# POWER.net
KiCad netlist of a schematic drawn in Altium Designer
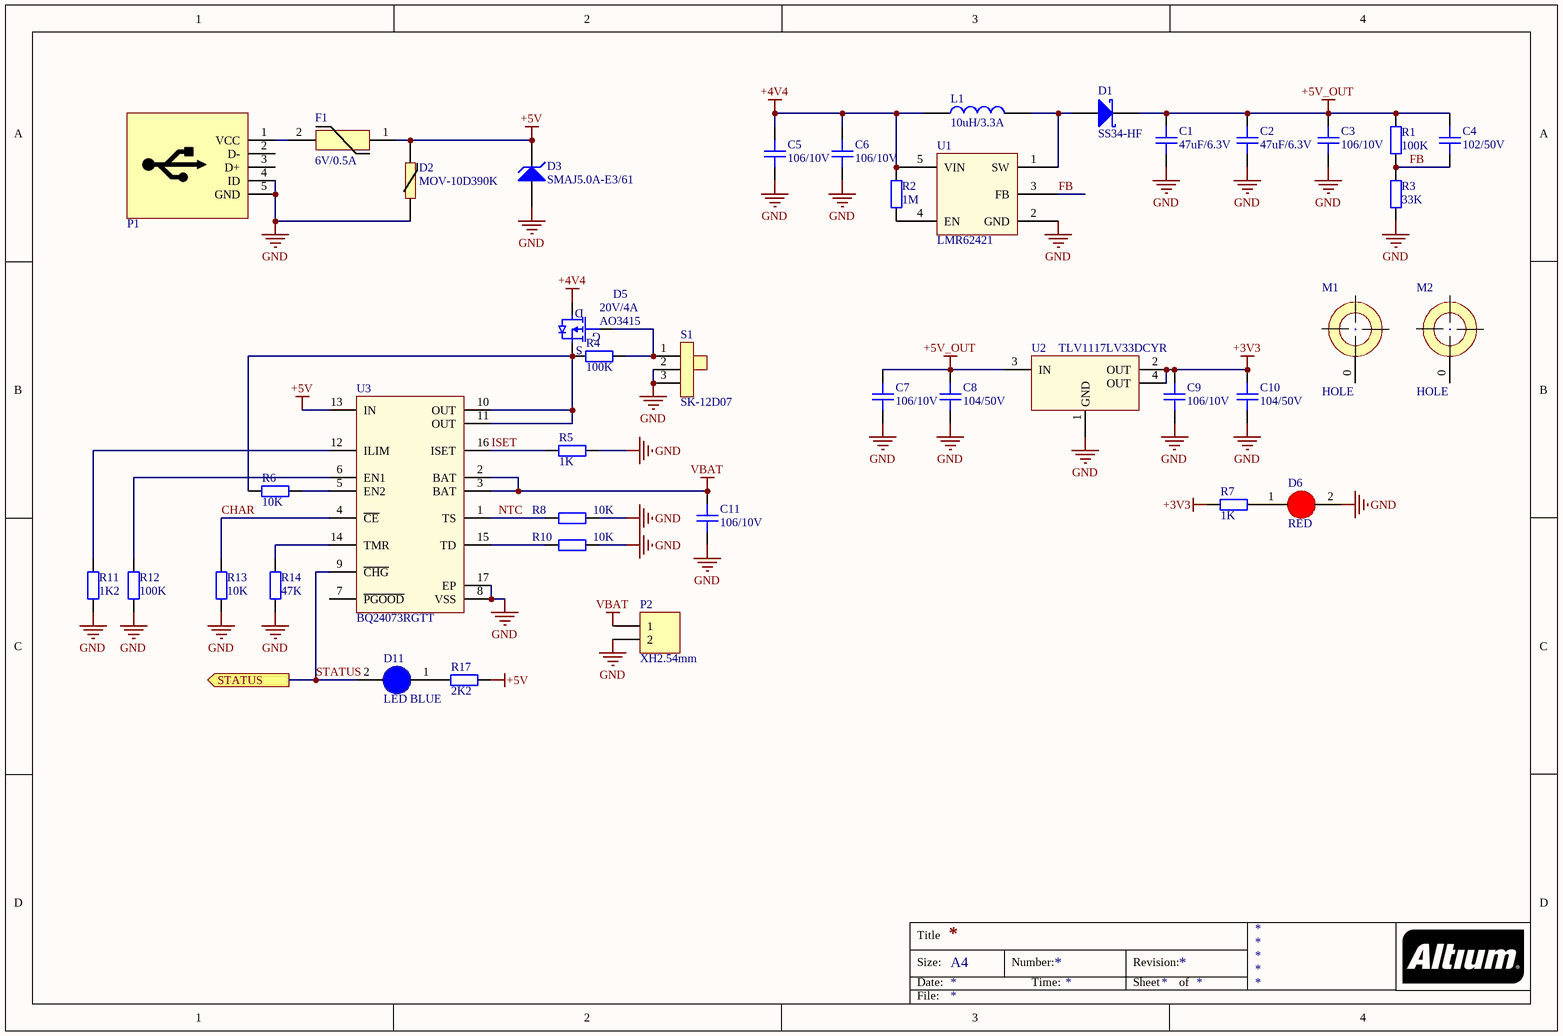
[diagram p0: POWER.SchDoc]

(export (version "E")
  (design (tool "Eeschema 10.0.6"))
  (components
    (comp (ref "C1")
      (value "47uF/6.3V")
      (footprint "CAPC-0603 (1608) - HD")
      (description "CAP CER 47UF 6.3V X5R 0603")
      (fields (field (name "MPN") "GRM188R60J476ME15D") (field (name "MFR") "Murata Electronics"))
      (libsource (lib "01.Passives 2") (part "GRM188R60J476ME15D"))
    )
    (comp (ref "C2")
      (value "47uF/6.3V")
      (footprint "CAPC-0603 (1608) - HD")
      (description "CAP CER 47UF 6.3V X5R 0603")
      (fields (field (name "MPN") "GRM188R60J476ME15D") (field (name "MFR") "Murata Electronics"))
      (libsource (lib "01.Passives 2") (part "GRM188R60J476ME15D"))
    )
    (comp (ref "C3")
      (value "106/10V")
      (footprint "CAPC-0603 (1608) - HD")
      (description "CAP CER 10uF 10% 10V X5R 0603")
      (fields (field (name "MPN") "CL10A106KP8NNNC") (field (name "MFR") "Samsung Electro-Mechanics"))
      (libsource (lib "01.Passives 2") (part "CL10A106KP8NNNC"))
    )
    (comp (ref "C4")
      (value "102/50V")
      (footprint "CAPC-0603 (1608) - HD")
      (description "CAP CER 1000pF 10% 50V X7R 0603")
      (fields (field (name "MPN") "CL10B102KB8NNNC"))
      (libsource (lib "01.Passives 2") (part "CL10B102KB8NNNC"))
    )
    (comp (ref "C5")
      (value "106/10V")
      (footprint "CAPC-0603 (1608) - HD")
      (description "CAP CER 10uF 10% 10V X5R 0603")
      (fields (field (name "MPN") "CL10A106KP8NNNC") (field (name "MFR") "Samsung Electro-Mechanics"))
      (libsource (lib "01.Passives 2") (part "CL10A106KP8NNNC"))
    )
    (comp (ref "C6")
      (value "106/10V")
      (footprint "CAPC-0603 (1608) - HD")
      (description "CAP CER 10uF 10% 10V X5R 0603")
      (fields (field (name "MPN") "CL10A106KP8NNNC") (field (name "MFR") "Samsung Electro-Mechanics"))
      (libsource (lib "01.Passives 2") (part "CL10A106KP8NNNC"))
    )
    (comp (ref "C7")
      (value "106/10V")
      (footprint "CAPC-0603 (1608) - HD")
      (description "CAP CER 10uF 10% 10V X5R 0603")
      (fields (field (name "MPN") "CL10A106KP8NNNC"))
      (libsource (lib "01.Passives") (part "CL10A106KP8NNNC"))
    )
    (comp (ref "C8")
      (value "104/50V")
      (footprint "CAPC-0603 (1608) - HD")
      (description "CAP CER 0.1uF 50V 10% X7R 0603")
      (fields (field (name "MPN") "C0603C104K5RACTU"))
      (libsource (lib "01.Passives") (part "C0603C104K5RACTU"))
    )
    (comp (ref "C9")
      (value "106/10V")
      (footprint "CAPC-0603 (1608) - HD")
      (description "CAP CER 10uF 10% 10V X5R 0603")
      (fields (field (name "MPN") "CL10A106KP8NNNC"))
      (libsource (lib "01.Passives") (part "CL10A106KP8NNNC"))
    )
    (comp (ref "C10")
      (value "104/50V")
      (footprint "CAPC-0603 (1608) - HD")
      (description "CAP CER 0.1uF 50V 10% X7R 0603")
      (fields (field (name "MPN") "C0603C104K5RACTU"))
      (libsource (lib "01.Passives") (part "C0603C104K5RACTU"))
    )
    (comp (ref "C11")
      (value "106/10V")
      (footprint "CAPC-0603 (1608) - HD")
      (description "CAP CER 10uF 10% 10V X5R 0603")
      (fields (field (name "MPN") "CL10A106KP8NNNC") (field (name "MFR") "Samsung Electro-Mechanics"))
      (libsource (lib "01.Passives 2") (part "CL10A106KP8NNNC"))
    )
    (comp (ref "D1")
      (value "SS34-HF")
      (footprint "DIODE_DO214AC_SMA")
      (description "DIODE SCHOTTKY 40V 3A SMA")
      (fields (field (name "MFR") "onsemi"))
      (libsource (lib "03.Semiconductor(1)") (part "SS34-HF"))
    )
    (comp (ref "D2")
      (value "MOV-10D390K")
      (footprint "MOV-07D101KTR")
      (description "VARISTOR 39V 500A DISC 10MM")
      (fields (field (name "MFR") "Bourns Inc.") (field (name "MPN") "MOV-10D390K"))
      (libsource (lib "01.Passives 2") (part "MOV-10D390K"))
    )
    (comp (ref "D3")
      (value "SMAJ5.0A-E3/61")
      (footprint "DIODE_DO214AC_SMA")
      (description "DIODE TVS 5VWM 9.2VC SMA")
      (libsource (lib "03.Semiconductor(1)") (part "SMAJ5.0A-E3/61"))
    )
    (comp (ref "D5")
      (value "20V/4A")
      (footprint "SOT23_3")
      (description "MOSFET P-CH 20V 4A SOT23")
      (fields (field (name "MFR") "Alpha & Omega Semiconductor Inc.") (field (name "MPN") "AO3415"))
      (libsource (lib "03.Semiconductor(1)") (part "AO3415"))
    )
    (comp (ref "D6")
      (value "RED")
      (footprint "LED 0603")
      (description "LED 0603 RED")
      (libsource (lib "03.Semiconductor(1)") (part "LED 0603 RED"))
    )
    (comp (ref "D11")
      (value "LED BLUE")
      (footprint "LED_3MM-RED - duplicate")
      (description "LED BLUE 3MM ROUND T/H")
      (fields (field (name "MPN") "LED BLUE 3MM") (field (name "MFR") "China"))
      (libsource (lib "03.Semiconductor(1)") (part "LED BLUE 3MM"))
    )
    (comp (ref "F1")
      (value "6V/0.5A")
      (footprint "FUSE 0ZCK_BEL")
      (description "PTC RESET FUSE 6V 500MA 0805")
      (fields (field (name "MPN") "0ZCK0050FF2E") (field (name "MANUFACTURER") "Bel Fuse Inc."))
      (libsource (lib "02.Power,Protection") (part "0ZCK0050FF2E"))
    )
    (comp (ref "L1")
      (value "10uH/3.3A")
      (footprint "IND-74404084150")
      (description "FIXED IND 10UH 3.3A 38 MOHM SMD")
      (fields
        (field (name "MPN") "SWPA8040S100MT")
        (field (name "MFR") "Shenzhen Sunlord Electronics Co., Ltd.")
      )
      (libsource (lib "01.Passives 2") (part "SWPA8040S100MT"))
    )
    (comp (ref "M1")
      (value "HOLE")
      (footprint "HOLE_3MM_6MM")
      (description "HOLE 2_4/2_5/3_5/3_6")
      (fields (field (name "MPN") "None"))
      (libsource (lib "04.Header-Connecter") (part "HOLE_2_4/2_5/3_5/3_6"))
    )
    (comp (ref "M2")
      (value "HOLE")
      (footprint "HOLE_3MM_6MM")
      (description "HOLE 2_4/2_5/3_5/3_6")
      (fields (field (name "MPN") "None"))
      (libsource (lib "04.Header-Connecter") (part "HOLE_2_4/2_5/3_5/3_6"))
    )
    (comp (ref "P1")
      (value "Micro USB")
      (footprint "MK5P MICROUSB")
      (description "Micro USB Right Angle MK5P DIP")
      (fields (field (name "MPN") "MK5P_DIP") (field (name "MFR") "China"))
      (libsource (lib "04.Header-Connecter") (part "MK5P_DIP"))
    )
    (comp (ref "P2")
      (value "XH2.54mm")
      (footprint "XH2.54-2P")
      (description "XH2.54mmm - 2P 180 degree")
      (fields (field (name "MPN") "XH2.54-2P") (field (name "MFR") "China"))
      (libsource (lib "04.Header-Connecter") (part "XH2.54-2P"))
    )
    (comp (ref "R1")
      (value "100K")
      (footprint "RESC-0603 (1608) - HD")
      (description "RES SMD 100K OHM 1% 1/10W 0603")
      (fields (field (name "MPN") "RC0603FR-07100KL") (field (name "MFR") "Yageo"))
      (libsource (lib "01.Passives 2") (part "RC0603FR-07100KL"))
    )
    (comp (ref "R2")
      (value "1M")
      (footprint "RESC-0603 (1608) - HD")
      (description "RES SMD 1M OHM 1% 1/10W 0603")
      (fields (field (name "MPN") "CRCW06031M00FKEA") (field (name "MFR") "Vishay Dale"))
      (libsource (lib "01.Passives 2") (part "CRCW06031M00FKEA"))
    )
    (comp (ref "R3")
      (value "33K")
      (footprint "RESC-0603 (1608) - HD")
      (description "RES SMD 33K OHM 1% 1/10W 0603")
      (fields (field (name "MPN") "RC0603FR-0733KL"))
      (libsource (lib "01.Passives 2") (part "RC0603FR-0733KL"))
    )
    (comp (ref "R4")
      (value "100K")
      (footprint "RESC-0603 (1608) - HD")
      (description "RES SMD 100K OHM 1% 1/10W 0603")
      (fields (field (name "MPN") "RC0603FR-07100KL") (field (name "MFR") "Yageo"))
      (libsource (lib "") (part "RC0603FR-07100KL_1"))
    )
    (comp (ref "R5")
      (value "1K")
      (footprint "RESC-0603 (1608) - HD")
      (description "RES SMD 1 KOHM 1% 1/10W 0603")
      (fields (field (name "MPN") "RC0603FR-071KL"))
      (libsource (lib "01.Passives 2") (part "RC0603FR-071KL"))
    )
    (comp (ref "R6")
      (value "10K")
      (footprint "RESC-0603 (1608) - HD")
      (description "RES SMD 10K OHM 1% 1/10W 0603")
      (fields (field (name "MPN") "RC0603FR-0710KL"))
      (libsource (lib "") (part "RC0603FR-0710KL_1"))
    )
    (comp (ref "R7")
      (value "1K")
      (footprint "RESC-0603 (1608) - HD")
      (description "RES SMD 1 KOHM 1% 1/10W 0603")
      (fields (field (name "MPN") "RC0603FR-071KL"))
      (libsource (lib "01.Passives 2") (part "RC0603FR-071KL"))
    )
    (comp (ref "R8")
      (value "10K")
      (footprint "RESC-0603 (1608) - HD")
      (description "RES SMD 10K OHM 1% 1/10W 0603")
      (fields (field (name "MPN") "RC0603FR-0710KL"))
      (libsource (lib "") (part "RC0603FR-0710KL_1"))
    )
    (comp (ref "R10")
      (value "10K")
      (footprint "RESC-0603 (1608) - HD")
      (description "RES SMD 10K OHM 1% 1/10W 0603")
      (fields (field (name "MPN") "RC0603FR-0710KL"))
      (libsource (lib "") (part "RC0603FR-0710KL_1"))
    )
    (comp (ref "R11")
      (value "1K2")
      (footprint "RESC-0603 (1608) - HD")
      (description "RES SMD 1.2K OHM 1% 1/10W 0603")
      (fields (field (name "MPN") "RC0603FR-071K2L"))
      (libsource (lib "01.Passives") (part "RC0603FR-071K2L"))
    )
    (comp (ref "R12")
      (value "100K")
      (footprint "RESC-0603 (1608) - HD")
      (description "RES SMD 100K OHM 1% 1/10W 0603")
      (fields (field (name "MPN") "RC0603FR-07100KL"))
      (libsource (lib "01.Passives") (part "RC0603FR-07100KL"))
    )
    (comp (ref "R13")
      (value "10K")
      (footprint "RESC-0603 (1608) - HD")
      (description "RES SMD 10K OHM 1% 1/10W 0603")
      (fields (field (name "MPN") "RC0603FR-0710KL"))
      (libsource (lib "01.Passives") (part "RC0603FR-0710KL"))
    )
    (comp (ref "R14")
      (value "47K")
      (footprint "RESC-0603 (1608) - HD")
      (description "RES SMD 47K OHM 1% 1/10W 0603")
      (fields (field (name "MPN") "RC0603FR0747KL"))
      (libsource (lib "01.Passives") (part "RC0603FR0747KL"))
    )
    (comp (ref "R17")
      (value "2K2")
      (footprint "RESC-0603 (1608) - HD")
      (description "RES SMD 2.2K OHM 1% 1/10W 0603")
      (fields (field (name "MPN") "CRCW06032K20FKEA"))
      (libsource (lib "01.Passives") (part "CRCW06032K20FKEA"))
    )
    (comp (ref "S1")
      (value "SK-12D07")
      (footprint "SK-12D07")
      (description "SK-12D07 Switch 5P")
      (fields (field (name "MFR") "ChinaDaier"))
      (libsource (lib "08.Miscellaneous") (part "SK-12D07"))
    )
    (comp (ref "U1")
      (value "LMR62421")
      (footprint "SC-74A")
      (description "IC REG BST SEPIC ADJ 2.1A SOT23")
      (fields (field (name "MPN") "LMR62421XMFX/NOPB") (field (name "MFR") "TI"))
      (libsource (lib "05.IC(1)") (part "LMR62421XMFX/NOPB"))
    )
    (comp (ref "U2")
      (value "TLV1117LV33DCYR")
      (footprint "SOT-223-4")
      (description "IC REG LINEAR 3.3V 1A SOT223-4")
      (libsource (lib "05.IC") (part "TLV1117LV33DCYR"))
    )
    (comp (ref "U3")
      (value "BQ24073RGTT")
      (footprint "RGT16-1700X1700TP")
      (description "IC LI-ION CHARGE/PWR MGMT 16-QFN")
      (fields (field (name "MFR") "Texas Instruments"))
      (libsource (lib "05.IC") (part "BQ24073RGTT"))
    )
  )
  (nets
    (net (code "1") (name "+3V3") (class "Default")
      (node (ref "C10") (pin "2") (pinfunction "2_2") (pintype "passive"))
      (node (ref "C9") (pin "2") (pinfunction "2_2") (pintype "passive"))
      (node (ref "R7") (pin "1") (pinfunction "1_1") (pintype "passive"))
      (node (ref "U2") (pin "2") (pinfunction "OUT_2") (pintype "passive"))
      (node (ref "U2") (pin "4") (pinfunction "OUT_4") (pintype "passive"))
    )
    (net (code "2") (name "+4V4") (class "Default")
      (node (ref "C5") (pin "2") (pinfunction "2_2") (pintype "passive"))
      (node (ref "C6") (pin "2") (pinfunction "2_2") (pintype "passive"))
      (node (ref "D5") (pin "3") (pinfunction "D_3") (pintype "passive"))
      (node (ref "L1") (pin "1") (pinfunction "1_1") (pintype "passive"))
      (node (ref "R2") (pin "2") (pinfunction "2_2") (pintype "passive"))
      (node (ref "U1") (pin "5") (pinfunction "VIN_5") (pintype "passive"))
    )
    (net (code "3") (name "+5V") (class "Default")
      (node (ref "D2") (pin "2") (pinfunction "K_2") (pintype "passive"))
      (node (ref "D3") (pin "2") (pinfunction "K_2") (pintype "passive"))
      (node (ref "F1") (pin "1") (pinfunction "1_1") (pintype "passive"))
      (node (ref "R17") (pin "2") (pinfunction "2_2") (pintype "passive"))
      (node (ref "U3") (pin "13") (pinfunction "IN_13") (pintype "power_in"))
    )
    (net (code "4") (name "+5V_OUT") (class "Default")
      (node (ref "C1") (pin "2") (pinfunction "2_2") (pintype "passive"))
      (node (ref "C2") (pin "2") (pinfunction "2_2") (pintype "passive"))
      (node (ref "C3") (pin "2") (pinfunction "2_2") (pintype "passive"))
      (node (ref "C4") (pin "2") (pinfunction "2_2") (pintype "passive"))
      (node (ref "C7") (pin "2") (pinfunction "2_2") (pintype "passive"))
      (node (ref "C8") (pin "2") (pinfunction "2_2") (pintype "passive"))
      (node (ref "D1") (pin "2") (pinfunction "K_2") (pintype "passive"))
      (node (ref "R1") (pin "2") (pinfunction "2_2") (pintype "passive"))
      (node (ref "U2") (pin "3") (pinfunction "IN_3") (pintype "passive"))
    )
    (net (code "5") (name "/CHAR") (class "Default")
      (node (ref "R13") (pin "2") (pinfunction "2_2") (pintype "passive"))
      (node (ref "U3") (pin "4") (pinfunction "~{CE}_4") (pintype "passive"))
    )
    (net (code "6") (name "/FB") (class "Default")
      (node (ref "C4") (pin "1") (pinfunction "1_1") (pintype "passive"))
      (node (ref "R1") (pin "1") (pinfunction "1_1") (pintype "passive"))
      (node (ref "R3") (pin "2") (pinfunction "2_2") (pintype "passive"))
      (node (ref "U1") (pin "3") (pinfunction "FB_3") (pintype "passive"))
    )
    (net (code "7") (name "/ISET") (class "Default")
      (node (ref "R5") (pin "1") (pinfunction "1_1") (pintype "passive"))
      (node (ref "U3") (pin "16") (pinfunction "ISET_16") (pintype "power_in"))
    )
    (net (code "8") (name "/NTC") (class "Default")
      (node (ref "R8") (pin "1") (pinfunction "1_1") (pintype "passive"))
      (node (ref "U3") (pin "1") (pinfunction "TS_1") (pintype "power_in"))
    )
    (net (code "9") (name "/STATUS") (class "Default")
      (node (ref "D11") (pin "2") (pinfunction "K_2") (pintype "passive"))
      (node (ref "U3") (pin "9") (pinfunction "~{CHG}_9") (pintype "power_in"))
    )
    (net (code "10") (name "GND") (class "Default")
      (node (ref "C1") (pin "1") (pinfunction "1_1") (pintype "passive"))
      (node (ref "C10") (pin "1") (pinfunction "1_1") (pintype "passive"))
      (node (ref "C11") (pin "1") (pinfunction "1_1") (pintype "passive"))
      (node (ref "C2") (pin "1") (pinfunction "1_1") (pintype "passive"))
      (node (ref "C3") (pin "1") (pinfunction "1_1") (pintype "passive"))
      (node (ref "C5") (pin "1") (pinfunction "1_1") (pintype "passive"))
      (node (ref "C6") (pin "1") (pinfunction "1_1") (pintype "passive"))
      (node (ref "C7") (pin "1") (pinfunction "1_1") (pintype "passive"))
      (node (ref "C8") (pin "1") (pinfunction "1_1") (pintype "passive"))
      (node (ref "C9") (pin "1") (pinfunction "1_1") (pintype "passive"))
      (node (ref "D2") (pin "1") (pinfunction "A_1") (pintype "passive"))
      (node (ref "D3") (pin "1") (pinfunction "A_1") (pintype "passive"))
      (node (ref "D6") (pin "2") (pinfunction "K_2") (pintype "passive"))
      (node (ref "P1") (pin "4") (pinfunction "ID_4") (pintype "passive"))
      (node (ref "P1") (pin "5") (pinfunction "GND_5") (pintype "passive"))
      (node (ref "P2") (pin "2") (pinfunction "2_2") (pintype "passive"))
      (node (ref "R10") (pin "2") (pinfunction "2_2") (pintype "passive"))
      (node (ref "R11") (pin "1") (pinfunction "1_1") (pintype "passive"))
      (node (ref "R12") (pin "1") (pinfunction "1_1") (pintype "passive"))
      (node (ref "R13") (pin "1") (pinfunction "1_1") (pintype "passive"))
      (node (ref "R14") (pin "1") (pinfunction "1_1") (pintype "passive"))
      (node (ref "R3") (pin "1") (pinfunction "1_1") (pintype "passive"))
      (node (ref "R5") (pin "2") (pinfunction "2_2") (pintype "passive"))
      (node (ref "R8") (pin "2") (pinfunction "2_2") (pintype "passive"))
      (node (ref "S1") (pin "2") (pinfunction "+_2") (pintype "power_in"))
      (node (ref "S1") (pin "3") (pinfunction "+_3") (pintype "power_in"))
      (node (ref "U1") (pin "2") (pinfunction "GND_2") (pintype "passive"))
      (node (ref "U2") (pin "1") (pinfunction "GND_1") (pintype "passive"))
      (node (ref "U3") (pin "17") (pinfunction "EP_17") (pintype "power_in"))
      (node (ref "U3") (pin "8") (pinfunction "VSS_8") (pintype "power_in"))
    )
    (net (code "11") (name "Net-(D1-A)") (class "Default")
      (node (ref "D1") (pin "1") (pinfunction "A_1") (pintype "passive"))
      (node (ref "L1") (pin "2") (pinfunction "2_2") (pintype "passive"))
      (node (ref "U1") (pin "1") (pinfunction "SW_1") (pintype "passive"))
    )
    (net (code "12") (name "Net-(D5-G)") (class "Default")
      (node (ref "D5") (pin "1") (pinfunction "G_1") (pintype "passive"))
      (node (ref "R4") (pin "1") (pinfunction "1_1") (pintype "passive"))
      (node (ref "S1") (pin "1") (pinfunction "+_1") (pintype "power_in"))
    )
    (net (code "13") (name "Net-(D5-S)") (class "Default")
      (node (ref "D5") (pin "2") (pinfunction "S_2") (pintype "passive"))
      (node (ref "R4") (pin "2") (pinfunction "2_2") (pintype "passive"))
      (node (ref "R6") (pin "1") (pinfunction "1_1") (pintype "passive"))
      (node (ref "U3") (pin "10") (pinfunction "OUT_10") (pintype "power_in"))
      (node (ref "U3") (pin "11") (pinfunction "OUT_11") (pintype "power_in"))
    )
    (net (code "14") (name "Net-(D6-A)") (class "Default")
      (node (ref "D6") (pin "1") (pinfunction "A_1") (pintype "passive"))
      (node (ref "R7") (pin "2") (pinfunction "2_2") (pintype "passive"))
    )
    (net (code "15") (name "Net-(D11-A)") (class "Default")
      (node (ref "D11") (pin "1") (pinfunction "A_1") (pintype "passive"))
      (node (ref "R17") (pin "1") (pinfunction "1_1") (pintype "passive"))
    )
    (net (code "16") (name "Net-(P1-VCC)") (class "Default")
      (node (ref "F1") (pin "2") (pinfunction "2_2") (pintype "passive"))
      (node (ref "P1") (pin "1") (pinfunction "VCC_1") (pintype "passive"))
    )
    (net (code "17") (name "Net-(U1-EN)") (class "Default")
      (node (ref "R2") (pin "1") (pinfunction "1_1") (pintype "passive"))
      (node (ref "U1") (pin "4") (pinfunction "EN_4") (pintype "passive"))
    )
    (net (code "18") (name "Net-(U3-EN1)") (class "Default")
      (node (ref "R12") (pin "2") (pinfunction "2_2") (pintype "passive"))
      (node (ref "U3") (pin "6") (pinfunction "EN1_6") (pintype "power_in"))
    )
    (net (code "19") (name "Net-(U3-EN2)") (class "Default")
      (node (ref "R6") (pin "2") (pinfunction "2_2") (pintype "passive"))
      (node (ref "U3") (pin "5") (pinfunction "EN2_5") (pintype "power_in"))
    )
    (net (code "20") (name "Net-(U3-ILIM)") (class "Default")
      (node (ref "R11") (pin "2") (pinfunction "2_2") (pintype "passive"))
      (node (ref "U3") (pin "12") (pinfunction "ILIM_12") (pintype "power_in"))
    )
    (net (code "21") (name "Net-(U3-TD)") (class "Default")
      (node (ref "R10") (pin "1") (pinfunction "1_1") (pintype "passive"))
      (node (ref "U3") (pin "15") (pinfunction "TD_15") (pintype "power_in"))
    )
    (net (code "22") (name "Net-(U3-TMR)") (class "Default")
      (node (ref "R14") (pin "2") (pinfunction "2_2") (pintype "passive"))
      (node (ref "U3") (pin "14") (pinfunction "TMR_14") (pintype "power_in"))
    )
    (net (code "23") (name "VBAT") (class "Default")
      (node (ref "C11") (pin "2") (pinfunction "2_2") (pintype "passive"))
      (node (ref "P2") (pin "1") (pinfunction "1_1") (pintype "passive"))
      (node (ref "U3") (pin "2") (pinfunction "BAT_2") (pintype "power_in"))
      (node (ref "U3") (pin "3") (pinfunction "BAT_3") (pintype "power_in"))
    )
    (net (code "24") (name "unconnected-(M1-Pad0)") (class "Default")
      (node (ref "M1") (pin "0") (pinfunction "0_0") (pintype "passive"))
    )
    (net (code "25") (name "unconnected-(M2-Pad0)") (class "Default")
      (node (ref "M2") (pin "0") (pinfunction "0_0") (pintype "passive"))
    )
    (net (code "26") (name "unconnected-(P1-D+-Pad3)") (class "Default")
      (node (ref "P1") (pin "3") (pinfunction "D+_3") (pintype "passive"))
    )
    (net (code "27") (name "unconnected-(P1-D--Pad2)") (class "Default")
      (node (ref "P1") (pin "2") (pinfunction "D-_2") (pintype "passive"))
    )
    (net (code "28") (name "unconnected-(U3-~{PGOOD}-Pad7)") (class "Default")
      (node (ref "U3") (pin "7") (pinfunction "~{PGOOD}_7") (pintype "power_in"))
    )
  )
)
